# S602K.net
KiCad netlist of a schematic drawn in EAGLE
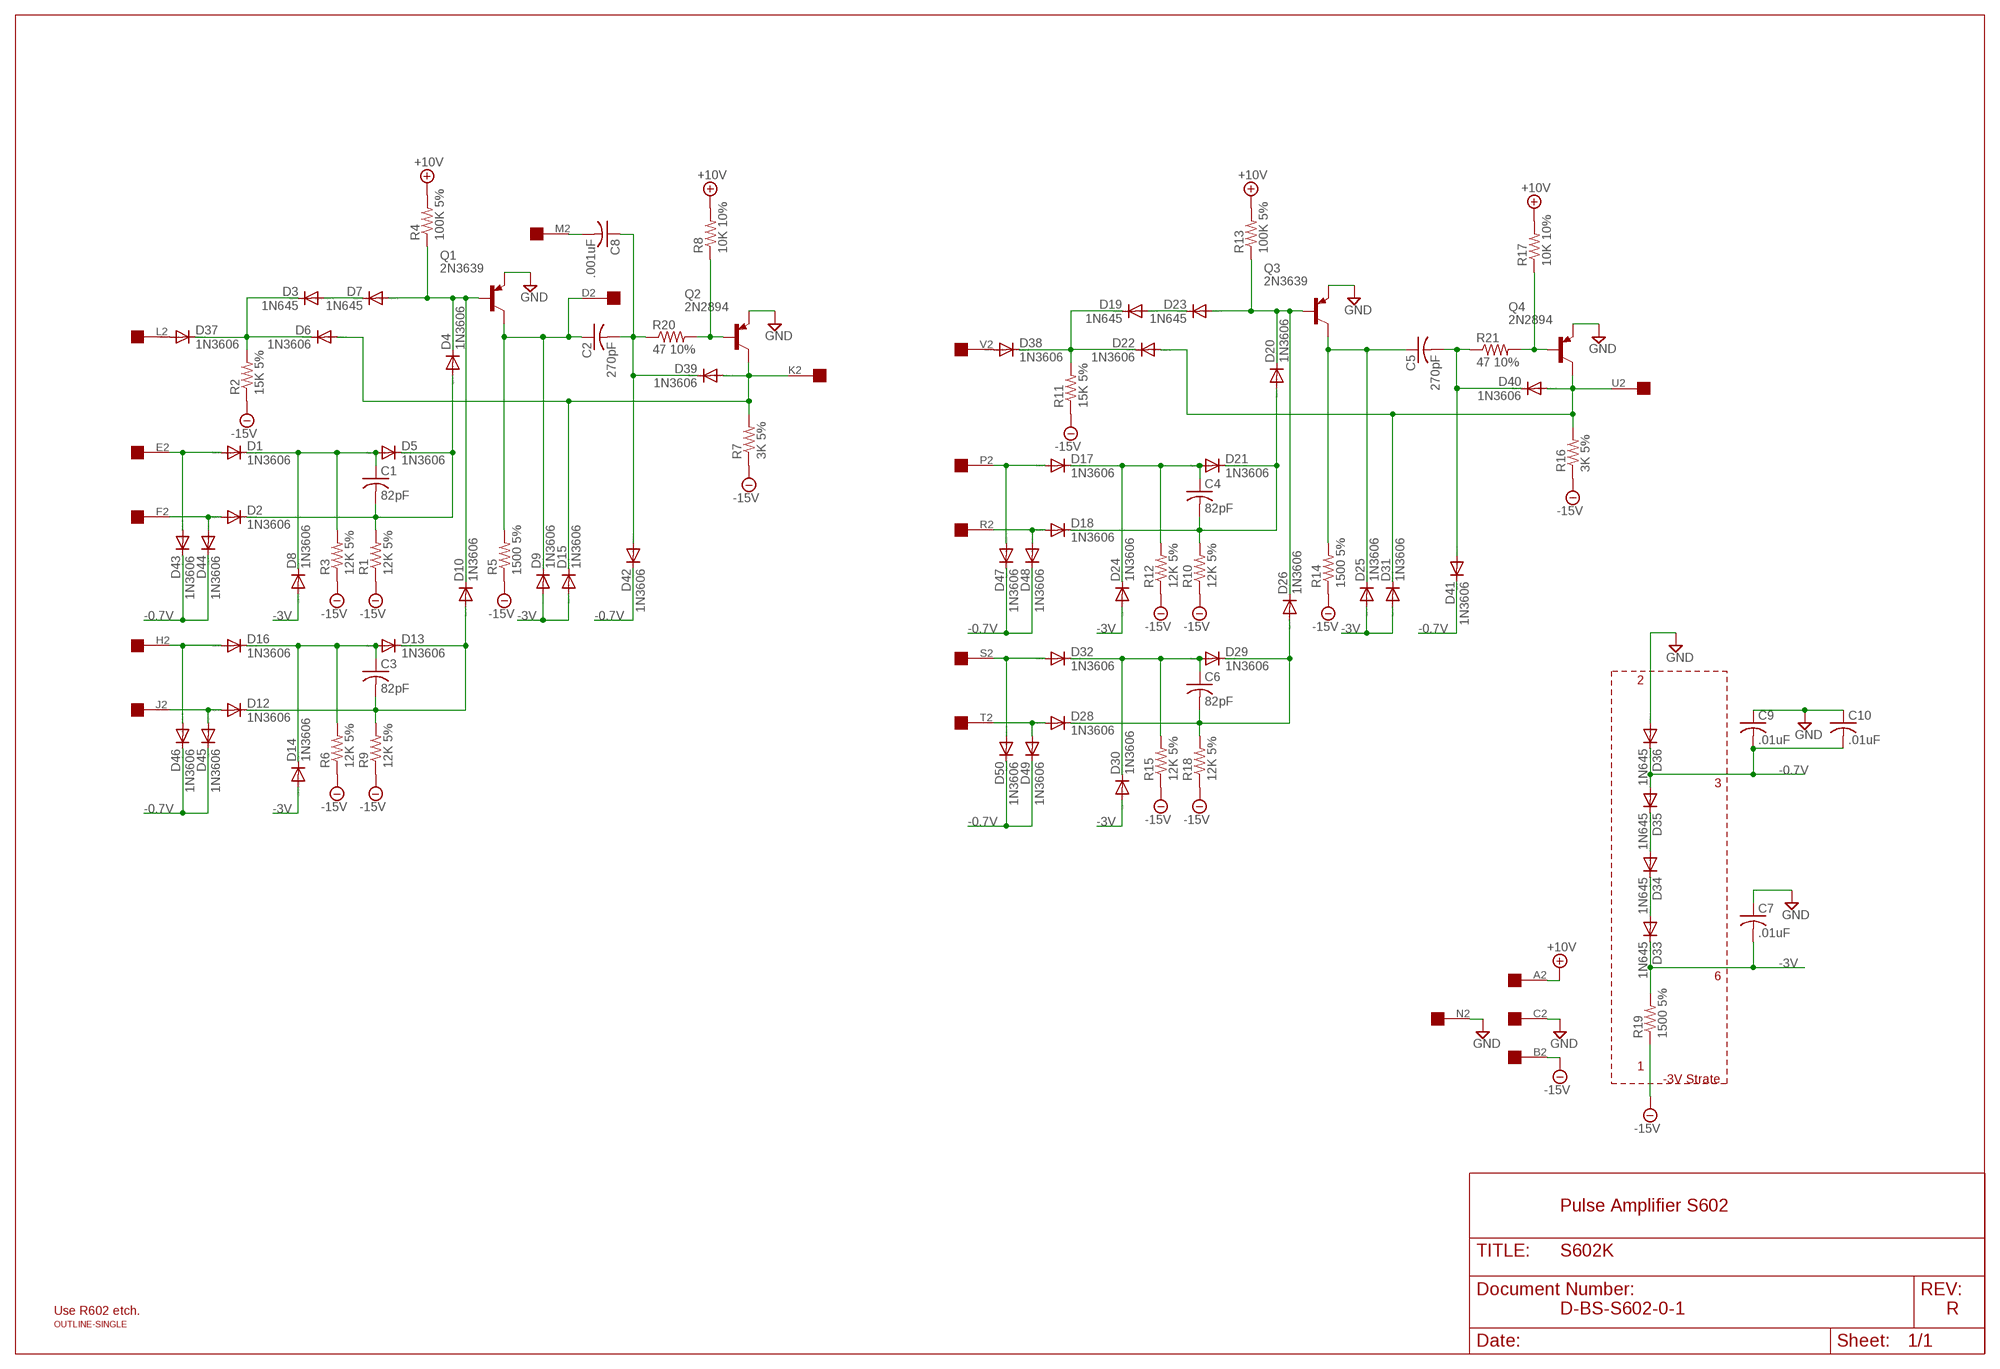
[diagram p0: schematic, sheet 1]

(export (version "E")
  (design (tool "Eeschema 10.0.6"))
  (components
    (comp (ref "C1")
      (value "82pF")
      (footprint "eagle-import:C050-025X075")
      (libsource (lib "eagle-import") (part "C-US050-025X075"))
    )
    (comp (ref "C2")
      (value "270pF")
      (footprint "eagle-import:C050-025X075")
      (libsource (lib "eagle-import") (part "C-US050-025X075"))
    )
    (comp (ref "C3")
      (value "82pF")
      (footprint "eagle-import:C050-025X075")
      (libsource (lib "eagle-import") (part "C-US050-025X075"))
    )
    (comp (ref "C4")
      (value "82pF")
      (footprint "eagle-import:C050-025X075")
      (libsource (lib "eagle-import") (part "C-US050-025X075"))
    )
    (comp (ref "C5")
      (value "270pF")
      (footprint "eagle-import:C050-025X075")
      (libsource (lib "eagle-import") (part "C-US050-025X075"))
    )
    (comp (ref "C6")
      (value "82pF")
      (footprint "eagle-import:C050-025X075")
      (libsource (lib "eagle-import") (part "C-US050-025X075"))
    )
    (comp (ref "C7")
      (value ".01uF")
      (footprint "eagle-import:C075-032X103")
      (libsource (lib "eagle-import") (part "C-US075-032X103"))
    )
    (comp (ref "C8")
      (value ".001uF")
      (footprint "eagle-import:C050-025X075")
      (libsource (lib "eagle-import") (part "C-US050-025X075"))
    )
    (comp (ref "C9")
      (value ".01uF")
      (footprint "eagle-import:C050-025X075")
      (libsource (lib "eagle-import") (part "C-US050-025X075"))
    )
    (comp (ref "C10")
      (value ".01uF")
      (footprint "eagle-import:C050-025X075")
      (libsource (lib "eagle-import") (part "C-US050-025X075"))
    )
    (comp (ref "D1")
      (value "1N3606")
      (footprint "eagle-import:DO35-10")
      (libsource (lib "eagle-import") (part "1N4148DO35-10"))
    )
    (comp (ref "D2")
      (value "1N3606")
      (footprint "eagle-import:DO35-10")
      (libsource (lib "eagle-import") (part "1N4148DO35-10"))
    )
    (comp (ref "D3")
      (value "1N645")
      (footprint "eagle-import:DO35-10")
      (libsource (lib "eagle-import") (part "1N4148DO35-10"))
    )
    (comp (ref "D4")
      (value "1N3606")
      (footprint "eagle-import:DO35-10")
      (libsource (lib "eagle-import") (part "1N4148DO35-10"))
    )
    (comp (ref "D5")
      (value "1N3606")
      (footprint "eagle-import:DO35-10")
      (libsource (lib "eagle-import") (part "1N4148DO35-10"))
    )
    (comp (ref "D6")
      (value "1N3606")
      (footprint "eagle-import:DO35-10")
      (libsource (lib "eagle-import") (part "1N4148DO35-10"))
    )
    (comp (ref "D7")
      (value "1N645")
      (footprint "eagle-import:DO35-10")
      (libsource (lib "eagle-import") (part "1N4148DO35-10"))
    )
    (comp (ref "D8")
      (value "1N3606")
      (footprint "eagle-import:DO35-10")
      (libsource (lib "eagle-import") (part "1N4148DO35-10"))
    )
    (comp (ref "D9")
      (value "1N3606")
      (footprint "eagle-import:DO35-10")
      (libsource (lib "eagle-import") (part "1N4148DO35-10"))
    )
    (comp (ref "D10")
      (value "1N3606")
      (footprint "eagle-import:DO35-10")
      (libsource (lib "eagle-import") (part "1N4148DO35-10"))
    )
    (comp (ref "D12")
      (value "1N3606")
      (footprint "eagle-import:DO35-10")
      (libsource (lib "eagle-import") (part "1N4148DO35-10"))
    )
    (comp (ref "D13")
      (value "1N3606")
      (footprint "eagle-import:DO35-10")
      (libsource (lib "eagle-import") (part "1N4148DO35-10"))
    )
    (comp (ref "D14")
      (value "1N3606")
      (footprint "eagle-import:DO35-10")
      (libsource (lib "eagle-import") (part "1N4148DO35-10"))
    )
    (comp (ref "D15")
      (value "1N3606")
      (footprint "eagle-import:DO35-10")
      (libsource (lib "eagle-import") (part "1N4148DO35-10"))
    )
    (comp (ref "D16")
      (value "1N3606")
      (footprint "eagle-import:DO35-10")
      (libsource (lib "eagle-import") (part "1N4148DO35-10"))
    )
    (comp (ref "D17")
      (value "1N3606")
      (footprint "eagle-import:DO35-10")
      (libsource (lib "eagle-import") (part "1N4148DO35-10"))
    )
    (comp (ref "D18")
      (value "1N3606")
      (footprint "eagle-import:DO35-10")
      (libsource (lib "eagle-import") (part "1N4148DO35-10"))
    )
    (comp (ref "D19")
      (value "1N645")
      (footprint "eagle-import:DO35-10")
      (libsource (lib "eagle-import") (part "1N4148DO35-10"))
    )
    (comp (ref "D20")
      (value "1N3606")
      (footprint "eagle-import:DO35-10")
      (libsource (lib "eagle-import") (part "1N4148DO35-10"))
    )
    (comp (ref "D21")
      (value "1N3606")
      (footprint "eagle-import:DO35-10")
      (libsource (lib "eagle-import") (part "1N4148DO35-10"))
    )
    (comp (ref "D22")
      (value "1N3606")
      (footprint "eagle-import:DO35-10")
      (libsource (lib "eagle-import") (part "1N4148DO35-10"))
    )
    (comp (ref "D23")
      (value "1N645")
      (footprint "eagle-import:DO35-10")
      (libsource (lib "eagle-import") (part "1N4148DO35-10"))
    )
    (comp (ref "D24")
      (value "1N3606")
      (footprint "eagle-import:DO35-10")
      (libsource (lib "eagle-import") (part "1N4148DO35-10"))
    )
    (comp (ref "D25")
      (value "1N3606")
      (footprint "eagle-import:DO35-10")
      (libsource (lib "eagle-import") (part "1N4148DO35-10"))
    )
    (comp (ref "D26")
      (value "1N3606")
      (footprint "eagle-import:DO35-10")
      (libsource (lib "eagle-import") (part "1N4148DO35-10"))
    )
    (comp (ref "D28")
      (value "1N3606")
      (footprint "eagle-import:DO35-10")
      (libsource (lib "eagle-import") (part "1N4148DO35-10"))
    )
    (comp (ref "D29")
      (value "1N3606")
      (footprint "eagle-import:DO35-10")
      (libsource (lib "eagle-import") (part "1N4148DO35-10"))
    )
    (comp (ref "D30")
      (value "1N3606")
      (footprint "eagle-import:DO35-10")
      (libsource (lib "eagle-import") (part "1N4148DO35-10"))
    )
    (comp (ref "D31")
      (value "1N3606")
      (footprint "eagle-import:DO35-10")
      (libsource (lib "eagle-import") (part "1N4148DO35-10"))
    )
    (comp (ref "D32")
      (value "1N3606")
      (footprint "eagle-import:DO35-10")
      (libsource (lib "eagle-import") (part "1N4148DO35-10"))
    )
    (comp (ref "D33")
      (value "1N645")
      (footprint "eagle-import:DO35-10")
      (libsource (lib "eagle-import") (part "1N4148DO35-10"))
    )
    (comp (ref "D34")
      (value "1N645")
      (footprint "eagle-import:DO35-10")
      (libsource (lib "eagle-import") (part "1N4148DO35-10"))
    )
    (comp (ref "D35")
      (value "1N645")
      (footprint "eagle-import:DO35-10")
      (libsource (lib "eagle-import") (part "1N4148DO35-10"))
    )
    (comp (ref "D36")
      (value "1N645")
      (footprint "eagle-import:DO35-10")
      (libsource (lib "eagle-import") (part "1N4148DO35-10"))
    )
    (comp (ref "D37")
      (value "1N3606")
      (footprint "eagle-import:DO35-10")
      (libsource (lib "eagle-import") (part "1N4148DO35-10"))
    )
    (comp (ref "D38")
      (value "1N3606")
      (footprint "eagle-import:DO35-10")
      (libsource (lib "eagle-import") (part "1N4148DO35-10"))
    )
    (comp (ref "D39")
      (value "1N3606")
      (footprint "eagle-import:DO35-10")
      (libsource (lib "eagle-import") (part "1N4148DO35-10"))
    )
    (comp (ref "D40")
      (value "1N3606")
      (footprint "eagle-import:DO35-10")
      (libsource (lib "eagle-import") (part "1N4148DO35-10"))
    )
    (comp (ref "D41")
      (value "1N3606")
      (footprint "eagle-import:DO35-10")
      (libsource (lib "eagle-import") (part "1N4148DO35-10"))
    )
    (comp (ref "D42")
      (value "1N3606")
      (footprint "eagle-import:DO35-10")
      (libsource (lib "eagle-import") (part "1N4148DO35-10"))
    )
    (comp (ref "D43")
      (value "1N3606")
      (footprint "eagle-import:DO35-10")
      (libsource (lib "eagle-import") (part "1N4148DO35-10"))
    )
    (comp (ref "D44")
      (value "1N3606")
      (footprint "eagle-import:DO35-10")
      (libsource (lib "eagle-import") (part "1N4148DO35-10"))
    )
    (comp (ref "D45")
      (value "1N3606")
      (footprint "eagle-import:DO35-10")
      (libsource (lib "eagle-import") (part "1N4148DO35-10"))
    )
    (comp (ref "D46")
      (value "1N3606")
      (footprint "eagle-import:DO35-10")
      (libsource (lib "eagle-import") (part "1N4148DO35-10"))
    )
    (comp (ref "D47")
      (value "1N3606")
      (footprint "eagle-import:DO35-10")
      (libsource (lib "eagle-import") (part "1N4148DO35-10"))
    )
    (comp (ref "D48")
      (value "1N3606")
      (footprint "eagle-import:DO35-10")
      (libsource (lib "eagle-import") (part "1N4148DO35-10"))
    )
    (comp (ref "D49")
      (value "1N3606")
      (footprint "eagle-import:DO35-10")
      (libsource (lib "eagle-import") (part "1N4148DO35-10"))
    )
    (comp (ref "D50")
      (value "1N3606")
      (footprint "eagle-import:DO35-10")
      (libsource (lib "eagle-import") (part "1N4148DO35-10"))
    )
    (comp (ref "Q1")
      (value "2N3639")
      (footprint "eagle-import:TO39")
      (libsource (lib "eagle-import") (part "2N2904"))
    )
    (comp (ref "Q2")
      (value "2N2894")
      (footprint "eagle-import:TO39")
      (libsource (lib "eagle-import") (part "2N2904"))
    )
    (comp (ref "Q3")
      (value "2N3639")
      (footprint "eagle-import:TO39")
      (libsource (lib "eagle-import") (part "2N2904"))
    )
    (comp (ref "Q4")
      (value "2N2894")
      (footprint "eagle-import:TO39")
      (libsource (lib "eagle-import") (part "2N2904"))
    )
    (comp (ref "R1")
      (value "12K 5%")
      (footprint "eagle-import:0207_10")
      (libsource (lib "eagle-import") (part "R-US_0207/10"))
    )
    (comp (ref "R2")
      (value "15K 5%")
      (footprint "eagle-import:0207_10")
      (libsource (lib "eagle-import") (part "R-US_0207/10"))
    )
    (comp (ref "R3")
      (value "12K 5%")
      (footprint "eagle-import:0207_10")
      (libsource (lib "eagle-import") (part "R-US_0207/10"))
    )
    (comp (ref "R4")
      (value "100K 5%")
      (footprint "eagle-import:0207_10")
      (libsource (lib "eagle-import") (part "R-US_0207/10"))
    )
    (comp (ref "R5")
      (value "1500 5%")
      (footprint "eagle-import:0207_10")
      (libsource (lib "eagle-import") (part "R-US_0207/10"))
    )
    (comp (ref "R6")
      (value "12K 5%")
      (footprint "eagle-import:0207_10")
      (libsource (lib "eagle-import") (part "R-US_0207/10"))
    )
    (comp (ref "R7")
      (value "3K 5%")
      (footprint "eagle-import:0207_10")
      (libsource (lib "eagle-import") (part "R-US_0207/10"))
    )
    (comp (ref "R8")
      (value "10K 10%")
      (footprint "eagle-import:0207_10")
      (libsource (lib "eagle-import") (part "R-US_0207/10"))
    )
    (comp (ref "R9")
      (value "12K 5%")
      (footprint "eagle-import:0207_10")
      (libsource (lib "eagle-import") (part "R-US_0207/10"))
    )
    (comp (ref "R10")
      (value "12K 5%")
      (footprint "eagle-import:0207_10")
      (libsource (lib "eagle-import") (part "R-US_0207/10"))
    )
    (comp (ref "R11")
      (value "15K 5%")
      (footprint "eagle-import:0207_10")
      (libsource (lib "eagle-import") (part "R-US_0207/10"))
    )
    (comp (ref "R12")
      (value "12K 5%")
      (footprint "eagle-import:0207_10")
      (libsource (lib "eagle-import") (part "R-US_0207/10"))
    )
    (comp (ref "R13")
      (value "100K 5%")
      (footprint "eagle-import:0207_10")
      (libsource (lib "eagle-import") (part "R-US_0207/10"))
    )
    (comp (ref "R14")
      (value "1500 5%")
      (footprint "eagle-import:0207_10")
      (libsource (lib "eagle-import") (part "R-US_0207/10"))
    )
    (comp (ref "R15")
      (value "12K 5%")
      (footprint "eagle-import:0207_10")
      (libsource (lib "eagle-import") (part "R-US_0207/10"))
    )
    (comp (ref "R16")
      (value "3K 5%")
      (footprint "eagle-import:0207_10")
      (libsource (lib "eagle-import") (part "R-US_0207/10"))
    )
    (comp (ref "R17")
      (value "10K 10%")
      (footprint "eagle-import:0207_10")
      (libsource (lib "eagle-import") (part "R-US_0207/10"))
    )
    (comp (ref "R18")
      (value "12K 5%")
      (footprint "eagle-import:0207_10")
      (libsource (lib "eagle-import") (part "R-US_0207/10"))
    )
    (comp (ref "R19")
      (value "1500 5%")
      (footprint "eagle-import:0207_10")
      (libsource (lib "eagle-import") (part "R-US_0207/10"))
    )
    (comp (ref "R20")
      (value "47 10%")
      (footprint "eagle-import:0207_10")
      (libsource (lib "eagle-import") (part "R-US_0207/10"))
    )
    (comp (ref "R21")
      (value "47 10%")
      (footprint "eagle-import:0207_10")
      (libsource (lib "eagle-import") (part "R-US_0207/10"))
    )
    (comp (ref "U$1")
      (value "OUTLINE-SINGLE")
      (footprint "eagle-import:SINGLE")
      (libsource (lib "eagle-import") (part "OUTLINE-SINGLE"))
    )
    (comp (ref "U$2")
      (value "EDGE-1")
      (footprint "eagle-import:EDGE-CON1")
      (libsource (lib "eagle-import") (part "EDGE-1"))
    )
  )
  (nets
    (net (code "1") (name "+10V") (class "Default")
      (node (ref "R13") (pin "2") (pinfunction "2_2") (pintype "passive"))
      (node (ref "R17") (pin "2") (pinfunction "2_2") (pintype "passive"))
      (node (ref "R4") (pin "2") (pinfunction "2_2") (pintype "passive"))
      (node (ref "R8") (pin "2") (pinfunction "2_2") (pintype "passive"))
      (node (ref "U$2") (pin "A2") (pinfunction "1_A2") (pintype "bidirectional"))
    )
    (net (code "2") (name "-15V") (class "Default")
      (node (ref "R1") (pin "1") (pinfunction "1_1") (pintype "passive"))
      (node (ref "R10") (pin "1") (pinfunction "1_1") (pintype "passive"))
      (node (ref "R11") (pin "1") (pinfunction "1_1") (pintype "passive"))
      (node (ref "R12") (pin "1") (pinfunction "1_1") (pintype "passive"))
      (node (ref "R14") (pin "1") (pinfunction "1_1") (pintype "passive"))
      (node (ref "R15") (pin "1") (pinfunction "1_1") (pintype "passive"))
      (node (ref "R16") (pin "1") (pinfunction "1_1") (pintype "passive"))
      (node (ref "R18") (pin "1") (pinfunction "1_1") (pintype "passive"))
      (node (ref "R19") (pin "1") (pinfunction "1_1") (pintype "passive"))
      (node (ref "R2") (pin "1") (pinfunction "1_1") (pintype "passive"))
      (node (ref "R3") (pin "1") (pinfunction "1_1") (pintype "passive"))
      (node (ref "R5") (pin "1") (pinfunction "1_1") (pintype "passive"))
      (node (ref "R6") (pin "1") (pinfunction "1_1") (pintype "passive"))
      (node (ref "R7") (pin "1") (pinfunction "1_1") (pintype "passive"))
      (node (ref "R9") (pin "1") (pinfunction "1_1") (pintype "passive"))
      (node (ref "U$2") (pin "B2") (pinfunction "1_B2") (pintype "bidirectional"))
    )
    (net (code "3") (name "/-0.7V") (class "Default")
      (node (ref "C10") (pin "2") (pinfunction "2_2") (pintype "passive"))
      (node (ref "C9") (pin "2") (pinfunction "2_2") (pintype "passive"))
      (node (ref "D35") (pin "A") (pinfunction "A_A") (pintype "passive"))
      (node (ref "D36") (pin "C") (pinfunction "C_C") (pintype "passive"))
      (node (ref "D41") (pin "C") (pinfunction "C_C") (pintype "passive"))
      (node (ref "D42") (pin "C") (pinfunction "C_C") (pintype "passive"))
      (node (ref "D43") (pin "C") (pinfunction "C_C") (pintype "passive"))
      (node (ref "D44") (pin "C") (pinfunction "C_C") (pintype "passive"))
      (node (ref "D45") (pin "C") (pinfunction "C_C") (pintype "passive"))
      (node (ref "D46") (pin "C") (pinfunction "C_C") (pintype "passive"))
      (node (ref "D47") (pin "C") (pinfunction "C_C") (pintype "passive"))
      (node (ref "D48") (pin "C") (pinfunction "C_C") (pintype "passive"))
      (node (ref "D49") (pin "C") (pinfunction "C_C") (pintype "passive"))
      (node (ref "D50") (pin "C") (pinfunction "C_C") (pintype "passive"))
    )
    (net (code "4") (name "/-3V") (class "Default")
      (node (ref "C7") (pin "2") (pinfunction "2_2") (pintype "passive"))
      (node (ref "D14") (pin "A") (pinfunction "A_A") (pintype "passive"))
      (node (ref "D15") (pin "A") (pinfunction "A_A") (pintype "passive"))
      (node (ref "D24") (pin "A") (pinfunction "A_A") (pintype "passive"))
      (node (ref "D25") (pin "A") (pinfunction "A_A") (pintype "passive"))
      (node (ref "D30") (pin "A") (pinfunction "A_A") (pintype "passive"))
      (node (ref "D31") (pin "A") (pinfunction "A_A") (pintype "passive"))
      (node (ref "D33") (pin "C") (pinfunction "C_C") (pintype "passive"))
      (node (ref "D8") (pin "A") (pinfunction "A_A") (pintype "passive"))
      (node (ref "D9") (pin "A") (pinfunction "A_A") (pintype "passive"))
      (node (ref "R19") (pin "2") (pinfunction "2_2") (pintype "passive"))
    )
    (net (code "5") (name "GND") (class "Default")
      (node (ref "C10") (pin "1") (pinfunction "1_1") (pintype "passive"))
      (node (ref "C7") (pin "1") (pinfunction "1_1") (pintype "passive"))
      (node (ref "C9") (pin "1") (pinfunction "1_1") (pintype "passive"))
      (node (ref "D36") (pin "A") (pinfunction "A_A") (pintype "passive"))
      (node (ref "Q1") (pin "1") (pinfunction "E_1") (pintype "passive"))
      (node (ref "Q2") (pin "1") (pinfunction "E_1") (pintype "passive"))
      (node (ref "Q3") (pin "1") (pinfunction "E_1") (pintype "passive"))
      (node (ref "Q4") (pin "1") (pinfunction "E_1") (pintype "passive"))
      (node (ref "U$2") (pin "C2") (pinfunction "1_C2") (pintype "bidirectional"))
      (node (ref "U$2") (pin "N2") (pinfunction "1_N2") (pintype "bidirectional"))
    )
    (net (code "6") (name "Net-(C1-Pad1)") (class "Default")
      (node (ref "C1") (pin "1") (pinfunction "1_1") (pintype "passive"))
      (node (ref "D1") (pin "C") (pinfunction "C_C") (pintype "passive"))
      (node (ref "D5") (pin "A") (pinfunction "A_A") (pintype "passive"))
      (node (ref "D8") (pin "C") (pinfunction "C_C") (pintype "passive"))
      (node (ref "R3") (pin "2") (pinfunction "2_2") (pintype "passive"))
    )
    (net (code "7") (name "Net-(C1-Pad2)") (class "Default")
      (node (ref "C1") (pin "2") (pinfunction "2_2") (pintype "passive"))
      (node (ref "D2") (pin "C") (pinfunction "C_C") (pintype "passive"))
      (node (ref "D4") (pin "A") (pinfunction "A_A") (pintype "passive"))
      (node (ref "D5") (pin "C") (pinfunction "C_C") (pintype "passive"))
      (node (ref "R1") (pin "2") (pinfunction "2_2") (pintype "passive"))
    )
    (net (code "8") (name "Net-(C2-Pad2)") (class "Default")
      (node (ref "C2") (pin "2") (pinfunction "2_2") (pintype "passive"))
      (node (ref "C8") (pin "1") (pinfunction "1_1") (pintype "passive"))
      (node (ref "D39") (pin "C") (pinfunction "C_C") (pintype "passive"))
      (node (ref "D42") (pin "A") (pinfunction "A_A") (pintype "passive"))
      (node (ref "R20") (pin "1") (pinfunction "1_1") (pintype "passive"))
    )
    (net (code "9") (name "Net-(C3-Pad1)") (class "Default")
      (node (ref "C3") (pin "1") (pinfunction "1_1") (pintype "passive"))
      (node (ref "D13") (pin "A") (pinfunction "A_A") (pintype "passive"))
      (node (ref "D14") (pin "C") (pinfunction "C_C") (pintype "passive"))
      (node (ref "D16") (pin "C") (pinfunction "C_C") (pintype "passive"))
      (node (ref "R6") (pin "2") (pinfunction "2_2") (pintype "passive"))
    )
    (net (code "10") (name "Net-(C3-Pad2)") (class "Default")
      (node (ref "C3") (pin "2") (pinfunction "2_2") (pintype "passive"))
      (node (ref "D10") (pin "A") (pinfunction "A_A") (pintype "passive"))
      (node (ref "D12") (pin "C") (pinfunction "C_C") (pintype "passive"))
      (node (ref "D13") (pin "C") (pinfunction "C_C") (pintype "passive"))
      (node (ref "R9") (pin "2") (pinfunction "2_2") (pintype "passive"))
    )
    (net (code "11") (name "Net-(C4-Pad1)") (class "Default")
      (node (ref "C4") (pin "1") (pinfunction "1_1") (pintype "passive"))
      (node (ref "D17") (pin "C") (pinfunction "C_C") (pintype "passive"))
      (node (ref "D21") (pin "A") (pinfunction "A_A") (pintype "passive"))
      (node (ref "D24") (pin "C") (pinfunction "C_C") (pintype "passive"))
      (node (ref "R12") (pin "2") (pinfunction "2_2") (pintype "passive"))
    )
    (net (code "12") (name "Net-(C4-Pad2)") (class "Default")
      (node (ref "C4") (pin "2") (pinfunction "2_2") (pintype "passive"))
      (node (ref "D18") (pin "C") (pinfunction "C_C") (pintype "passive"))
      (node (ref "D20") (pin "A") (pinfunction "A_A") (pintype "passive"))
      (node (ref "D21") (pin "C") (pinfunction "C_C") (pintype "passive"))
      (node (ref "R10") (pin "2") (pinfunction "2_2") (pintype "passive"))
    )
    (net (code "13") (name "Net-(C5-Pad2)") (class "Default")
      (node (ref "C5") (pin "2") (pinfunction "2_2") (pintype "passive"))
      (node (ref "D40") (pin "C") (pinfunction "C_C") (pintype "passive"))
      (node (ref "D41") (pin "A") (pinfunction "A_A") (pintype "passive"))
      (node (ref "R21") (pin "1") (pinfunction "1_1") (pintype "passive"))
    )
    (net (code "14") (name "Net-(C6-Pad1)") (class "Default")
      (node (ref "C6") (pin "1") (pinfunction "1_1") (pintype "passive"))
      (node (ref "D29") (pin "A") (pinfunction "A_A") (pintype "passive"))
      (node (ref "D30") (pin "C") (pinfunction "C_C") (pintype "passive"))
      (node (ref "D32") (pin "C") (pinfunction "C_C") (pintype "passive"))
      (node (ref "R15") (pin "2") (pinfunction "2_2") (pintype "passive"))
    )
    (net (code "15") (name "Net-(C6-Pad2)") (class "Default")
      (node (ref "C6") (pin "2") (pinfunction "2_2") (pintype "passive"))
      (node (ref "D26") (pin "A") (pinfunction "A_A") (pintype "passive"))
      (node (ref "D28") (pin "C") (pinfunction "C_C") (pintype "passive"))
      (node (ref "D29") (pin "C") (pinfunction "C_C") (pintype "passive"))
      (node (ref "R18") (pin "2") (pinfunction "2_2") (pintype "passive"))
    )
    (net (code "16") (name "Net-(D3-PadA)") (class "Default")
      (node (ref "D3") (pin "A") (pinfunction "A_A") (pintype "passive"))
      (node (ref "D7") (pin "C") (pinfunction "C_C") (pintype "passive"))
    )
    (net (code "17") (name "Net-(D3-PadC)") (class "Default")
      (node (ref "D3") (pin "C") (pinfunction "C_C") (pintype "passive"))
      (node (ref "D37") (pin "C") (pinfunction "C_C") (pintype "passive"))
      (node (ref "D6") (pin "C") (pinfunction "C_C") (pintype "passive"))
      (node (ref "R2") (pin "2") (pinfunction "2_2") (pintype "passive"))
    )
    (net (code "18") (name "Net-(D19-PadA)") (class "Default")
      (node (ref "D19") (pin "A") (pinfunction "A_A") (pintype "passive"))
      (node (ref "D23") (pin "C") (pinfunction "C_C") (pintype "passive"))
    )
    (net (code "19") (name "Net-(D19-PadC)") (class "Default")
      (node (ref "D19") (pin "C") (pinfunction "C_C") (pintype "passive"))
      (node (ref "D22") (pin "C") (pinfunction "C_C") (pintype "passive"))
      (node (ref "D38") (pin "C") (pinfunction "C_C") (pintype "passive"))
      (node (ref "R11") (pin "2") (pinfunction "2_2") (pintype "passive"))
    )
    (net (code "20") (name "Net-(D33-PadA)") (class "Default")
      (node (ref "D33") (pin "A") (pinfunction "A_A") (pintype "passive"))
      (node (ref "D34") (pin "C") (pinfunction "C_C") (pintype "passive"))
    )
    (net (code "21") (name "Net-(D34-PadA)") (class "Default")
      (node (ref "D34") (pin "A") (pinfunction "A_A") (pintype "passive"))
      (node (ref "D35") (pin "C") (pinfunction "C_C") (pintype "passive"))
    )
    (net (code "22") (name "Net-(Q1-B)") (class "Default")
      (node (ref "D10") (pin "C") (pinfunction "C_C") (pintype "passive"))
      (node (ref "D4") (pin "C") (pinfunction "C_C") (pintype "passive"))
      (node (ref "D7") (pin "A") (pinfunction "A_A") (pintype "passive"))
      (node (ref "Q1") (pin "2") (pinfunction "B_2") (pintype "passive"))
      (node (ref "R4") (pin "1") (pinfunction "1_1") (pintype "passive"))
    )
    (net (code "23") (name "Net-(Q1-C)") (class "Default")
      (node (ref "C2") (pin "1") (pinfunction "1_1") (pintype "passive"))
      (node (ref "D9") (pin "C") (pinfunction "C_C") (pintype "passive"))
      (node (ref "Q1") (pin "3") (pinfunction "C_3") (pintype "passive"))
      (node (ref "R5") (pin "2") (pinfunction "2_2") (pintype "passive"))
      (node (ref "U$2") (pin "D2") (pinfunction "1_D2") (pintype "bidirectional"))
    )
    (net (code "24") (name "Net-(Q2-B)") (class "Default")
      (node (ref "Q2") (pin "2") (pinfunction "B_2") (pintype "passive"))
      (node (ref "R20") (pin "2") (pinfunction "2_2") (pintype "passive"))
      (node (ref "R8") (pin "1") (pinfunction "1_1") (pintype "passive"))
    )
    (net (code "25") (name "Net-(Q2-C)") (class "Default")
      (node (ref "D15") (pin "C") (pinfunction "C_C") (pintype "passive"))
      (node (ref "D39") (pin "A") (pinfunction "A_A") (pintype "passive"))
      (node (ref "D6") (pin "A") (pinfunction "A_A") (pintype "passive"))
      (node (ref "Q2") (pin "3") (pinfunction "C_3") (pintype "passive"))
      (node (ref "R7") (pin "2") (pinfunction "2_2") (pintype "passive"))
      (node (ref "U$2") (pin "K2") (pinfunction "1_K2") (pintype "bidirectional"))
    )
    (net (code "26") (name "Net-(Q3-B)") (class "Default")
      (node (ref "D20") (pin "C") (pinfunction "C_C") (pintype "passive"))
      (node (ref "D23") (pin "A") (pinfunction "A_A") (pintype "passive"))
      (node (ref "D26") (pin "C") (pinfunction "C_C") (pintype "passive"))
      (node (ref "Q3") (pin "2") (pinfunction "B_2") (pintype "passive"))
      (node (ref "R13") (pin "1") (pinfunction "1_1") (pintype "passive"))
    )
    (net (code "27") (name "Net-(Q3-C)") (class "Default")
      (node (ref "C5") (pin "1") (pinfunction "1_1") (pintype "passive"))
      (node (ref "D25") (pin "C") (pinfunction "C_C") (pintype "passive"))
      (node (ref "Q3") (pin "3") (pinfunction "C_3") (pintype "passive"))
      (node (ref "R14") (pin "2") (pinfunction "2_2") (pintype "passive"))
    )
    (net (code "28") (name "Net-(Q4-B)") (class "Default")
      (node (ref "Q4") (pin "2") (pinfunction "B_2") (pintype "passive"))
      (node (ref "R17") (pin "1") (pinfunction "1_1") (pintype "passive"))
      (node (ref "R21") (pin "2") (pinfunction "2_2") (pintype "passive"))
    )
    (net (code "29") (name "Net-(Q4-C)") (class "Default")
      (node (ref "D22") (pin "A") (pinfunction "A_A") (pintype "passive"))
      (node (ref "D31") (pin "C") (pinfunction "C_C") (pintype "passive"))
      (node (ref "D40") (pin "A") (pinfunction "A_A") (pintype "passive"))
      (node (ref "Q4") (pin "3") (pinfunction "C_3") (pintype "passive"))
      (node (ref "R16") (pin "2") (pinfunction "2_2") (pintype "passive"))
      (node (ref "U$2") (pin "U2") (pinfunction "1_U2") (pintype "bidirectional"))
    )
    (net (code "30") (name "Net-(U$2E-1)") (class "Default")
      (node (ref "D1") (pin "A") (pinfunction "A_A") (pintype "passive"))
      (node (ref "D43") (pin "A") (pinfunction "A_A") (pintype "passive"))
      (node (ref "U$2") (pin "E2") (pinfunction "1_E2") (pintype "bidirectional"))
    )
    (net (code "31") (name "Net-(U$2F-1)") (class "Default")
      (node (ref "D2") (pin "A") (pinfunction "A_A") (pintype "passive"))
      (node (ref "D44") (pin "A") (pinfunction "A_A") (pintype "passive"))
      (node (ref "U$2") (pin "F2") (pinfunction "1_F2") (pintype "bidirectional"))
    )
    (net (code "32") (name "Net-(U$2G-1)") (class "Default")
      (node (ref "D16") (pin "A") (pinfunction "A_A") (pintype "passive"))
      (node (ref "D46") (pin "A") (pinfunction "A_A") (pintype "passive"))
      (node (ref "U$2") (pin "H2") (pinfunction "1_H2") (pintype "bidirectional"))
    )
    (net (code "33") (name "Net-(U$2H-1)") (class "Default")
      (node (ref "D12") (pin "A") (pinfunction "A_A") (pintype "passive"))
      (node (ref "D45") (pin "A") (pinfunction "A_A") (pintype "passive"))
      (node (ref "U$2") (pin "J2") (pinfunction "1_J2") (pintype "bidirectional"))
    )
    (net (code "34") (name "Net-(U$2J-1)") (class "Default")
      (node (ref "D37") (pin "A") (pinfunction "A_A") (pintype "passive"))
      (node (ref "U$2") (pin "L2") (pinfunction "1_L2") (pintype "bidirectional"))
    )
    (net (code "35") (name "Net-(U$2K-1)") (class "Default")
      (node (ref "C8") (pin "2") (pinfunction "2_2") (pintype "passive"))
      (node (ref "U$2") (pin "M2") (pinfunction "1_M2") (pintype "bidirectional"))
    )
    (net (code "36") (name "Net-(U$2M-1)") (class "Default")
      (node (ref "D17") (pin "A") (pinfunction "A_A") (pintype "passive"))
      (node (ref "D47") (pin "A") (pinfunction "A_A") (pintype "passive"))
      (node (ref "U$2") (pin "P2") (pinfunction "1_P2") (pintype "bidirectional"))
    )
    (net (code "37") (name "Net-(U$2N-1)") (class "Default")
      (node (ref "D18") (pin "A") (pinfunction "A_A") (pintype "passive"))
      (node (ref "D48") (pin "A") (pinfunction "A_A") (pintype "passive"))
      (node (ref "U$2") (pin "R2") (pinfunction "1_R2") (pintype "bidirectional"))
    )
    (net (code "38") (name "Net-(U$2O-1)") (class "Default")
      (node (ref "D32") (pin "A") (pinfunction "A_A") (pintype "passive"))
      (node (ref "D50") (pin "A") (pinfunction "A_A") (pintype "passive"))
      (node (ref "U$2") (pin "S2") (pinfunction "1_S2") (pintype "bidirectional"))
    )
    (net (code "39") (name "Net-(U$2P-1)") (class "Default")
      (node (ref "D28") (pin "A") (pinfunction "A_A") (pintype "passive"))
      (node (ref "D49") (pin "A") (pinfunction "A_A") (pintype "passive"))
      (node (ref "U$2") (pin "T2") (pinfunction "1_T2") (pintype "bidirectional"))
    )
    (net (code "40") (name "Net-(U$2R-1)") (class "Default")
      (node (ref "D38") (pin "A") (pinfunction "A_A") (pintype "passive"))
      (node (ref "U$2") (pin "V2") (pinfunction "1_V2") (pintype "bidirectional"))
    )
  )
)
